# MillBug.net
KiCad netlist of a schematic drawn in EAGLE
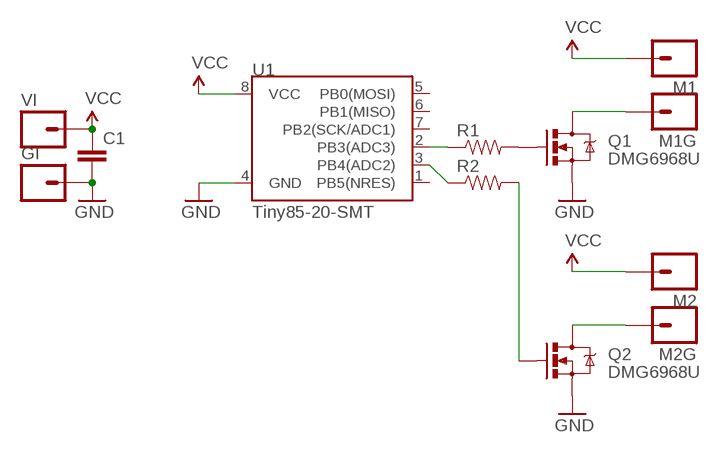
[diagram p0: schematic, sheet 1]

(export (version "E")
  (design (tool "Eeschema 10.0.6"))
  (components
    (comp (ref "C1")
      (value "CAP0603-CAP")
      (footprint "eagle-import:0603-CAP")
      (libsource (lib "eagle-import") (part "CAP0603-CAP"))
    )
    (comp (ref "GI")
      (value "M01PTH")
      (footprint "eagle-import:1X01")
      (libsource (lib "eagle-import") (part "M01PTH"))
    )
    (comp (ref "M1")
      (value "M01PTH")
      (footprint "eagle-import:1X01")
      (libsource (lib "eagle-import") (part "M01PTH"))
    )
    (comp (ref "M1G")
      (value "M01PTH")
      (footprint "eagle-import:1X01")
      (libsource (lib "eagle-import") (part "M01PTH"))
    )
    (comp (ref "M2")
      (value "M01PTH")
      (footprint "eagle-import:1X01")
      (libsource (lib "eagle-import") (part "M01PTH"))
    )
    (comp (ref "M2G")
      (value "M01PTH")
      (footprint "eagle-import:1X01")
      (libsource (lib "eagle-import") (part "M01PTH"))
    )
    (comp (ref "Q1")
      (value "DMG6968U")
      (footprint "eagle-import:SOT23-3")
      (libsource (lib "eagle-import") (part "MOSFET-NCHANNELBSS123LT1G"))
    )
    (comp (ref "Q2")
      (value "DMG6968U")
      (footprint "eagle-import:SOT23-3")
      (libsource (lib "eagle-import") (part "MOSFET-NCHANNELBSS123LT1G"))
    )
    (comp (ref "R1")
      (value "RESISTOR0603-RES")
      (footprint "eagle-import:0603-RES")
      (libsource (lib "eagle-import") (part "RESISTOR0603-RES"))
    )
    (comp (ref "R2")
      (value "RESISTOR0603-RES")
      (footprint "eagle-import:0603-RES")
      (libsource (lib "eagle-import") (part "RESISTOR0603-RES"))
    )
    (comp (ref "U1")
      (value "Tiny85-20-SMT")
      (footprint "eagle-import:SO08-EIAJ")
      (libsource (lib "eagle-import") (part "ATTINY45TINY85-20-SMT"))
    )
    (comp (ref "VI")
      (value "M01PTH")
      (footprint "eagle-import:1X01")
      (libsource (lib "eagle-import") (part "M01PTH"))
    )
  )
  (nets
    (net (code "1") (name "GND") (class "Default")
      (node (ref "C1") (pin "2") (pinfunction "2_2") (pintype "passive"))
      (node (ref "GI") (pin "1") (pinfunction "1_1") (pintype "passive"))
      (node (ref "Q1") (pin "2") (pinfunction "S_2") (pintype "passive"))
      (node (ref "Q2") (pin "2") (pinfunction "S_2") (pintype "passive"))
      (node (ref "U1") (pin "4") (pinfunction "GND_4") (pintype "bidirectional"))
    )
    (net (code "2") (name "Net-(Q1-D)") (class "Default")
      (node (ref "M1G") (pin "1") (pinfunction "1_1") (pintype "passive"))
      (node (ref "Q1") (pin "3") (pinfunction "D_3") (pintype "passive"))
    )
    (net (code "3") (name "Net-(Q1-G)") (class "Default")
      (node (ref "Q1") (pin "1") (pinfunction "G_1") (pintype "passive"))
      (node (ref "R1") (pin "2") (pinfunction "2_2") (pintype "passive"))
    )
    (net (code "4") (name "Net-(Q2-D)") (class "Default")
      (node (ref "M2G") (pin "1") (pinfunction "1_1") (pintype "passive"))
      (node (ref "Q2") (pin "3") (pinfunction "D_3") (pintype "passive"))
    )
    (net (code "5") (name "Net-(Q2-G)") (class "Default")
      (node (ref "Q2") (pin "1") (pinfunction "G_1") (pintype "passive"))
      (node (ref "R2") (pin "2") (pinfunction "2_2") (pintype "passive"))
    )
    (net (code "6") (name "Net-(U1-PB3(ADC3))") (class "Default")
      (node (ref "R1") (pin "1") (pinfunction "1_1") (pintype "passive"))
      (node (ref "U1") (pin "2") (pinfunction "PB3(ADC3)_2") (pintype "bidirectional"))
    )
    (net (code "7") (name "Net-(U1-PB4(ADC2))") (class "Default")
      (node (ref "R2") (pin "1") (pinfunction "1_1") (pintype "passive"))
      (node (ref "U1") (pin "3") (pinfunction "PB4(ADC2)_3") (pintype "bidirectional"))
    )
    (net (code "8") (name "VCC") (class "Default")
      (node (ref "C1") (pin "1") (pinfunction "1_1") (pintype "passive"))
      (node (ref "M1") (pin "1") (pinfunction "1_1") (pintype "passive"))
      (node (ref "M2") (pin "1") (pinfunction "1_1") (pintype "passive"))
      (node (ref "U1") (pin "8") (pinfunction "VCC_8") (pintype "bidirectional"))
      (node (ref "VI") (pin "1") (pinfunction "1_1") (pintype "passive"))
    )
    (net (code "9") (name "unconnected-(U1-PB0(MOSI)-Pad5)") (class "Default")
      (node (ref "U1") (pin "5") (pinfunction "PB0(MOSI)_5") (pintype "bidirectional"))
    )
    (net (code "10") (name "unconnected-(U1-PB1(MISO)-Pad6)") (class "Default")
      (node (ref "U1") (pin "6") (pinfunction "PB1(MISO)_6") (pintype "bidirectional"))
    )
    (net (code "11") (name "unconnected-(U1-PB2(SCK{slash}ADC1)-Pad7)") (class "Default")
      (node (ref "U1") (pin "7") (pinfunction "PB2(SCK/ADC1)_7") (pintype "bidirectional"))
    )
    (net (code "12") (name "unconnected-(U1-PB5(NRES)-Pad1)") (class "Default")
      (node (ref "U1") (pin "1") (pinfunction "PB5(NRES)_1") (pintype "bidirectional"))
    )
  )
)
